# espnative-deadrail-2-3.net
KiCad netlist of a schematic drawn in EAGLE
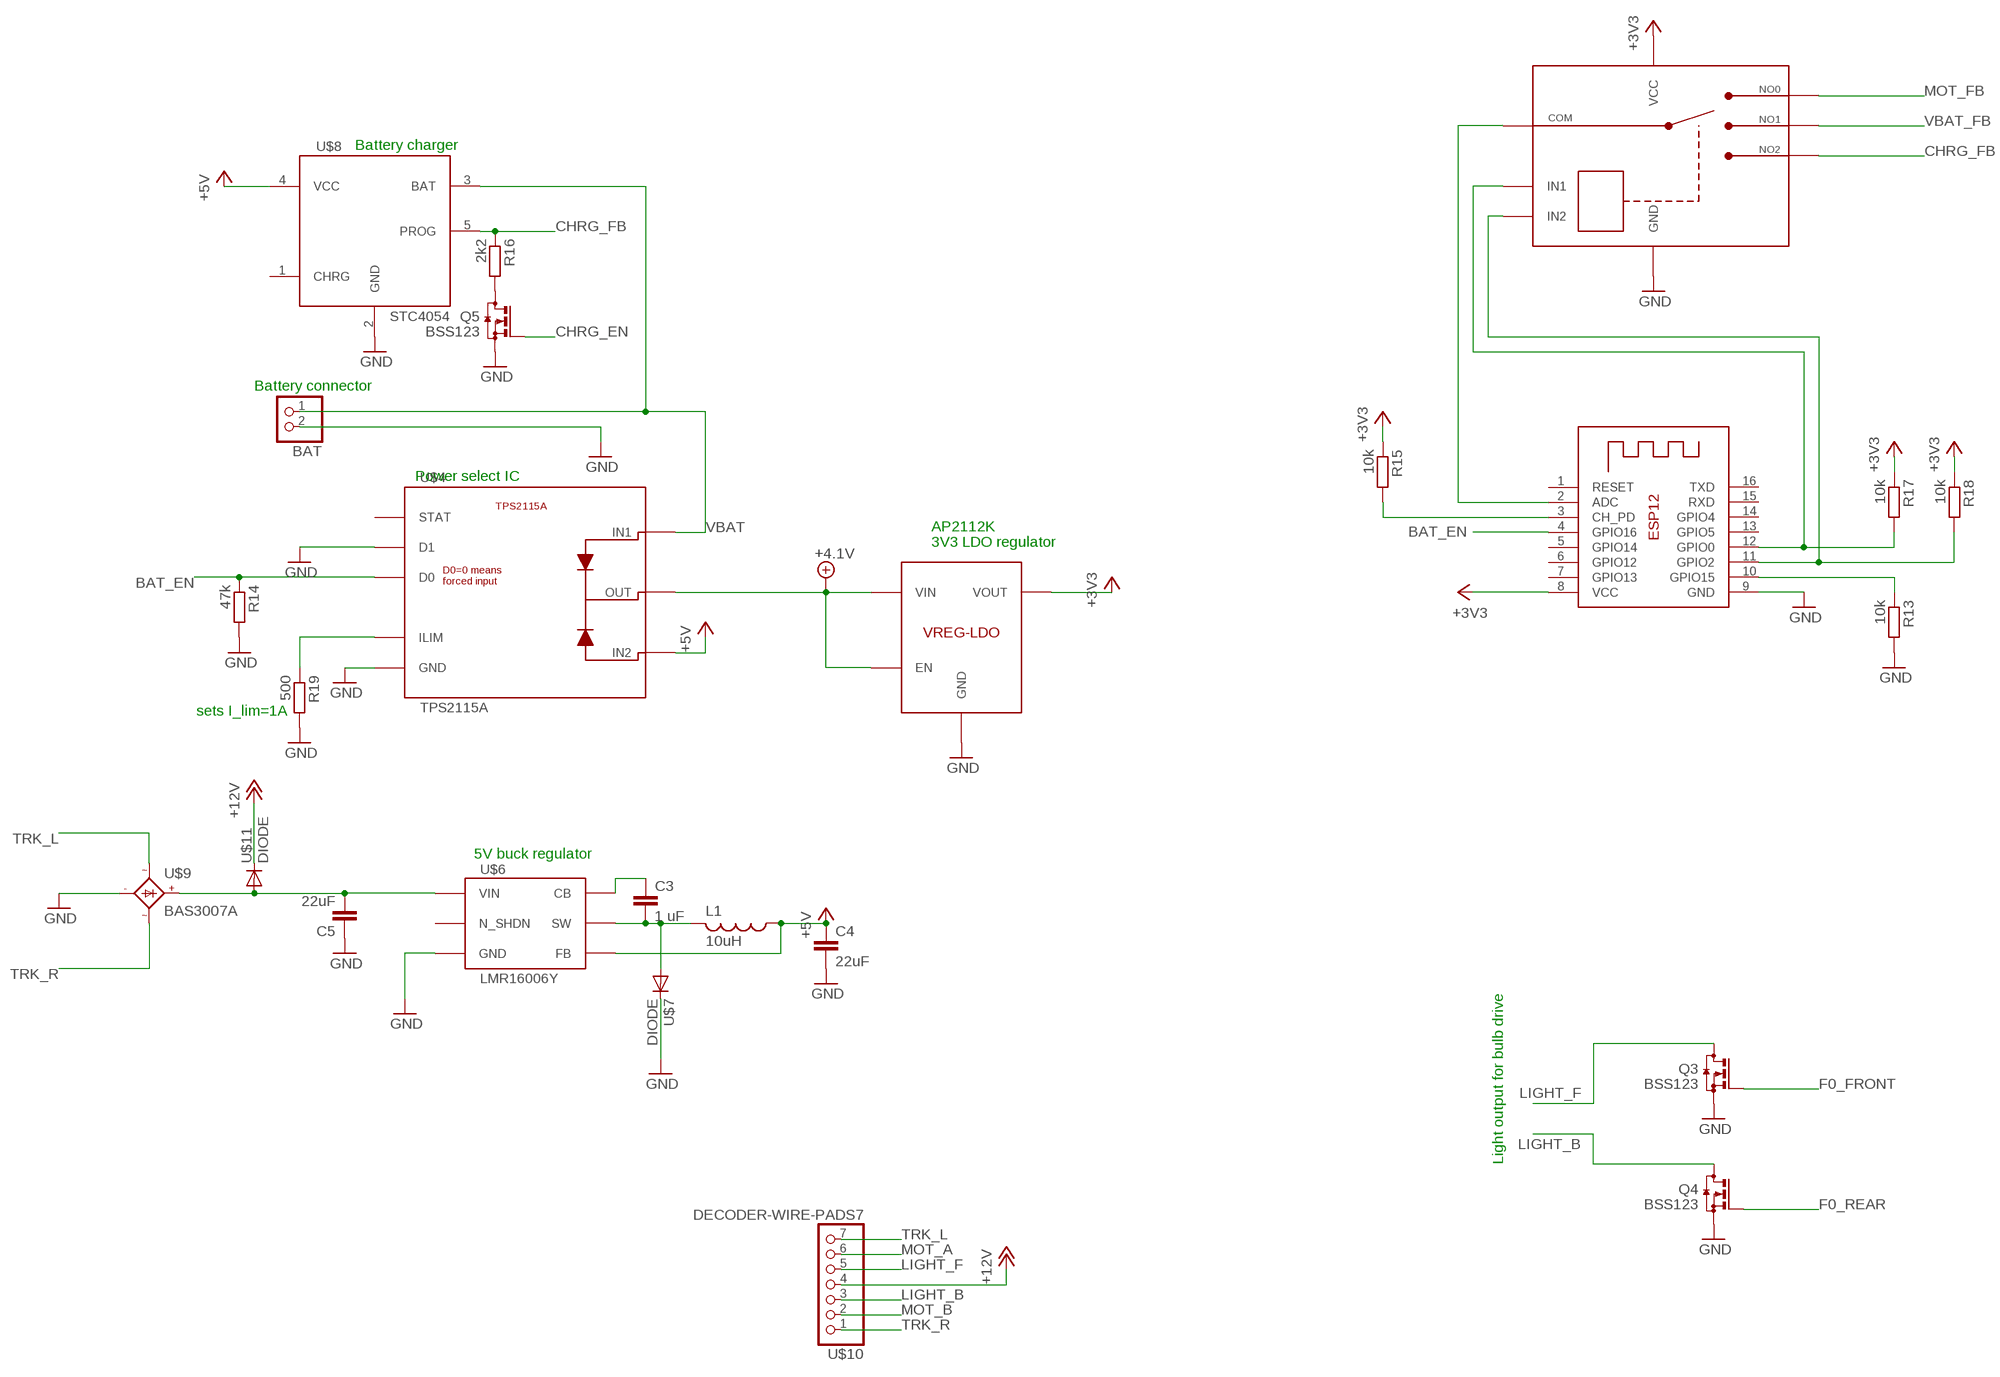
[diagram p0: schematic, sheet 1, part 1 of 2]
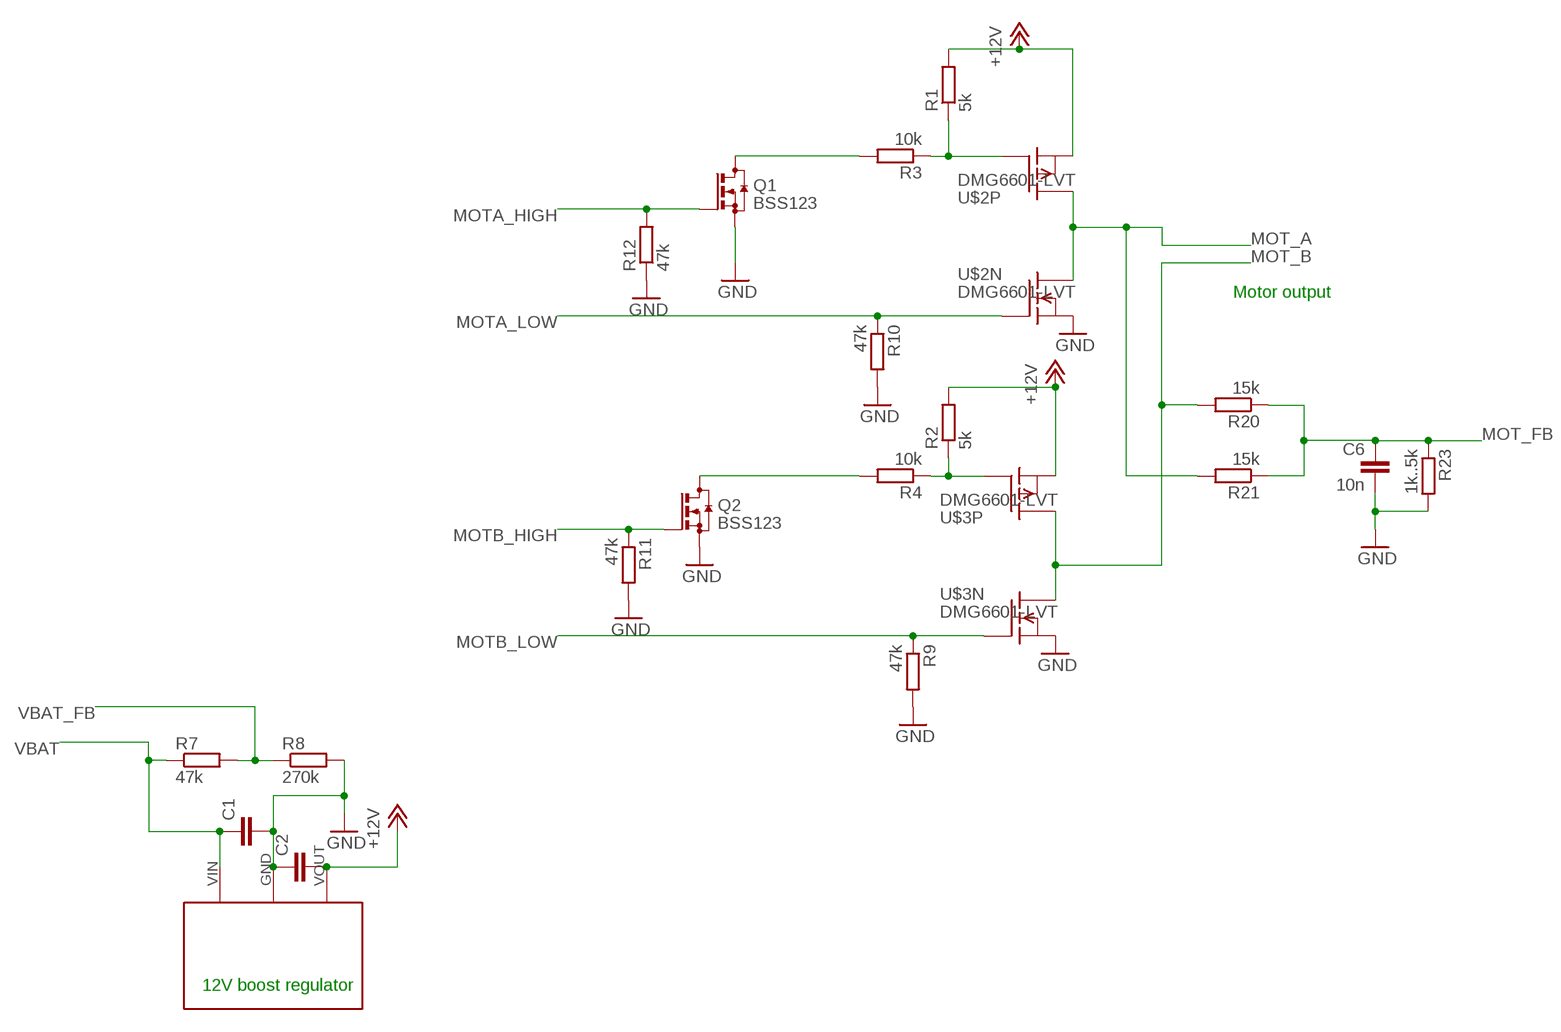
[diagram p1: schematic, sheet 1, part 2 of 2]

(export (version "E")
  (design (tool "Eeschema 10.0.6"))
  (components
    (comp (ref "BAT")
      (value "JST_2PIN-SMT-RA")
      (footprint "eagle-import:JST-PH-2-SMT-RA")
      (libsource (lib "eagle-import") (part "JST_2PIN-SMT-RA"))
    )
    (comp (ref "C1")
      (value "C-EUC1206")
      (footprint "eagle-import:C1206")
      (libsource (lib "eagle-import") (part "C-EUC1206"))
    )
    (comp (ref "C2")
      (value "C-EUC1206")
      (footprint "eagle-import:C1206")
      (libsource (lib "eagle-import") (part "C-EUC1206"))
    )
    (comp (ref "C3")
      (value "1 uF")
      (footprint "eagle-import:C0603")
      (libsource (lib "eagle-import") (part "C-EUC0603"))
    )
    (comp (ref "C4")
      (value "22uF")
      (footprint "eagle-import:C0603")
      (libsource (lib "eagle-import") (part "C-EUC0603"))
    )
    (comp (ref "C5")
      (value "22uF")
      (footprint "eagle-import:C1206")
      (libsource (lib "eagle-import") (part "C-EUC1206"))
    )
    (comp (ref "C6")
      (value "10n")
      (footprint "eagle-import:C0603")
      (libsource (lib "eagle-import") (part "C-EUC0603"))
    )
    (comp (ref "L1")
      (value "10uH")
      (footprint "eagle-import:FDSD0420")
      (libsource (lib "eagle-import") (part "FDSD0420"))
    )
    (comp (ref "Q1")
      (value "BSS123")
      (footprint "eagle-import:SOT23")
      (libsource (lib "eagle-import") (part "BSS123"))
    )
    (comp (ref "Q2")
      (value "BSS123")
      (footprint "eagle-import:SOT23")
      (libsource (lib "eagle-import") (part "BSS123"))
    )
    (comp (ref "Q3")
      (value "BSS123")
      (footprint "eagle-import:SOT23")
      (libsource (lib "eagle-import") (part "BSS123"))
    )
    (comp (ref "Q4")
      (value "BSS123")
      (footprint "eagle-import:SOT23")
      (libsource (lib "eagle-import") (part "BSS123"))
    )
    (comp (ref "Q5")
      (value "BSS123")
      (footprint "eagle-import:SOT23")
      (libsource (lib "eagle-import") (part "BSS123"))
    )
    (comp (ref "R1")
      (value "5k")
      (footprint "eagle-import:R0603")
      (libsource (lib "eagle-import") (part "R-EU_R0603"))
    )
    (comp (ref "R2")
      (value "5k")
      (footprint "eagle-import:R0603")
      (libsource (lib "eagle-import") (part "R-EU_R0603"))
    )
    (comp (ref "R3")
      (value "10k")
      (footprint "eagle-import:R0603")
      (libsource (lib "eagle-import") (part "R-EU_R0603"))
    )
    (comp (ref "R4")
      (value "10k")
      (footprint "eagle-import:R0603")
      (libsource (lib "eagle-import") (part "R-EU_R0603"))
    )
    (comp (ref "R7")
      (value "47k")
      (footprint "eagle-import:R0603")
      (libsource (lib "eagle-import") (part "R-EU_R0603"))
    )
    (comp (ref "R8")
      (value "270k")
      (footprint "eagle-import:R0603")
      (libsource (lib "eagle-import") (part "R-EU_R0603"))
    )
    (comp (ref "R9")
      (value "47k")
      (footprint "eagle-import:R0603")
      (libsource (lib "eagle-import") (part "R-EU_R0603"))
    )
    (comp (ref "R10")
      (value "47k")
      (footprint "eagle-import:R0603")
      (libsource (lib "eagle-import") (part "R-EU_R0603"))
    )
    (comp (ref "R11")
      (value "47k")
      (footprint "eagle-import:R0603")
      (libsource (lib "eagle-import") (part "R-EU_R0603"))
    )
    (comp (ref "R12")
      (value "47k")
      (footprint "eagle-import:R0603")
      (libsource (lib "eagle-import") (part "R-EU_R0603"))
    )
    (comp (ref "R13")
      (value "10k")
      (footprint "eagle-import:R0603")
      (libsource (lib "eagle-import") (part "R-EU_R0603"))
    )
    (comp (ref "R14")
      (value "47k")
      (footprint "eagle-import:R0603")
      (libsource (lib "eagle-import") (part "R-EU_R0603"))
    )
    (comp (ref "R15")
      (value "10k")
      (footprint "eagle-import:R0603")
      (libsource (lib "eagle-import") (part "R-EU_R0603"))
    )
    (comp (ref "R16")
      (value "2k2")
      (footprint "eagle-import:R0603")
      (libsource (lib "eagle-import") (part "R-EU_R0603"))
    )
    (comp (ref "R17")
      (value "10k")
      (footprint "eagle-import:R0603")
      (libsource (lib "eagle-import") (part "R-EU_R0603"))
    )
    (comp (ref "R18")
      (value "10k")
      (footprint "eagle-import:R0603")
      (libsource (lib "eagle-import") (part "R-EU_R0603"))
    )
    (comp (ref "R19")
      (value "500")
      (footprint "eagle-import:R0603")
      (libsource (lib "eagle-import") (part "R-EU_R0603"))
    )
    (comp (ref "R20")
      (value "15k")
      (footprint "eagle-import:R0603")
      (libsource (lib "eagle-import") (part "R-EU_R0603"))
    )
    (comp (ref "R21")
      (value "15k")
      (footprint "eagle-import:R0603")
      (libsource (lib "eagle-import") (part "R-EU_R0603"))
    )
    (comp (ref "R23")
      (value "1k..5k")
      (footprint "eagle-import:R0603")
      (libsource (lib "eagle-import") (part "R-EU_R0603"))
    )
    (comp (ref "U$1")
      (value "AP2112K-3V3")
      (footprint "eagle-import:SOT23-5L")
      (libsource (lib "eagle-import") (part "AP2112K"))
    )
    (comp (ref "U$2")
      (value "DMG6601-LVT")
      (footprint "eagle-import:TSOT-26")
      (libsource (lib "eagle-import") (part "DMG6601-LVT"))
    )
    (comp (ref "U$3")
      (value "DMG6601-LVT")
      (footprint "eagle-import:TSOT-26")
      (libsource (lib "eagle-import") (part "DMG6601-LVT"))
    )
    (comp (ref "U$4")
      (value "TPS2115A")
      (footprint "eagle-import:TSSOP-8")
      (libsource (lib "eagle-import") (part "TPS2115A"))
    )
    (comp (ref "U$5")
      (value "POLOLU-VREG12")
      (footprint "eagle-import:POLOLU-REGULATOR")
      (libsource (lib "eagle-import") (part "POLOLU-VREG12"))
    )
    (comp (ref "U$6")
      (value "LMR16006Y")
      (footprint "eagle-import:SOT23-6")
      (libsource (lib "eagle-import") (part "LMR16006Y"))
    )
    (comp (ref "U$7")
      (value "DIODE")
      (footprint "eagle-import:DIODE-1206")
      (libsource (lib "eagle-import") (part "DIODE"))
    )
    (comp (ref "U$8")
      (value "STC4054")
      (footprint "eagle-import:SOT23-5L")
      (libsource (lib "eagle-import") (part "STC4054"))
    )
    (comp (ref "U$9")
      (value "BAS3007A")
      (footprint "eagle-import:SOT143B")
      (libsource (lib "eagle-import") (part "BAS3007A"))
    )
    (comp (ref "U$10")
      (value "DECODER-WIRE-PADS7")
      (footprint "eagle-import:DECODER-WIRE-PADS")
      (libsource (lib "eagle-import") (part "DECODER-WIRE-PADS7"))
    )
    (comp (ref "U$11")
      (value "DIODE")
      (footprint "eagle-import:DIODE-1206")
      (libsource (lib "eagle-import") (part "DIODE"))
    )
    (comp (ref "U$12")
      (value "TS5A3359")
      (footprint "eagle-import:US8")
      (libsource (lib "eagle-import") (part "TS5A3359"))
    )
    (comp (ref "X1")
      (value "ESP-12")
      (footprint "eagle-import:ESP-12")
      (libsource (lib "eagle-import") (part "ESP-12"))
    )
  )
  (nets
    (net (code "1") (name "+3V3") (class "Default")
      (node (ref "R15") (pin "1") (pinfunction "1_1") (pintype "passive"))
      (node (ref "R17") (pin "1") (pinfunction "1_1") (pintype "passive"))
      (node (ref "R18") (pin "1") (pinfunction "1_1") (pintype "passive"))
      (node (ref "U$1") (pin "5") (pinfunction "VOUT_5") (pintype "bidirectional"))
      (node (ref "U$12") (pin "8") (pinfunction "VCC_8") (pintype "bidirectional"))
      (node (ref "X1") (pin "8") (pinfunction "VCC_8") (pintype "power_in"))
    )
    (net (code "2") (name "+4.1V") (class "Default")
      (node (ref "U$1") (pin "1") (pinfunction "VIN_1") (pintype "bidirectional"))
      (node (ref "U$1") (pin "3") (pinfunction "EN_3") (pintype "bidirectional"))
      (node (ref "U$4") (pin "7") (pinfunction "OUT_7") (pintype "bidirectional"))
    )
    (net (code "3") (name "+5V") (class "Default")
      (node (ref "C4") (pin "1") (pinfunction "1_1") (pintype "passive"))
      (node (ref "L1") (pin "P$1") (pinfunction "1_P$1") (pintype "passive"))
      (node (ref "U$4") (pin "6") (pinfunction "IN2_6") (pintype "bidirectional"))
      (node (ref "U$6") (pin "3") (pinfunction "FB_3") (pintype "bidirectional"))
      (node (ref "U$8") (pin "4") (pinfunction "VCC_4") (pintype "bidirectional"))
    )
    (net (code "4") (name "+12V") (class "Default")
      (node (ref "C2") (pin "2") (pinfunction "2_2") (pintype "passive"))
      (node (ref "R1") (pin "2") (pinfunction "2_2") (pintype "passive"))
      (node (ref "R2") (pin "2") (pinfunction "2_2") (pintype "passive"))
      (node (ref "U$10") (pin "4") (pinfunction "4_4") (pintype "passive"))
      (node (ref "U$11") (pin "C") (pinfunction "C_C") (pintype "passive"))
      (node (ref "U$2") (pin "2") (pinfunction "S_2") (pintype "passive"))
      (node (ref "U$3") (pin "2") (pinfunction "S_2") (pintype "passive"))
      (node (ref "U$5") (pin "VOUT") (pinfunction "VOUT_VOUT") (pintype "bidirectional"))
    )
    (net (code "5") (name "/BAT_EN") (class "Default")
      (node (ref "R14") (pin "1") (pinfunction "1_1") (pintype "passive"))
      (node (ref "U$4") (pin "2") (pinfunction "D0_2") (pintype "bidirectional"))
      (node (ref "X1") (pin "4") (pinfunction "GPIO16_4") (pintype "bidirectional"))
    )
    (net (code "6") (name "/CHRG_EN") (class "Default")
      (node (ref "Q5") (pin "1") (pinfunction "G_1") (pintype "passive"))
    )
    (net (code "7") (name "/CHRG_FB") (class "Default")
      (node (ref "R16") (pin "1") (pinfunction "1_1") (pintype "passive"))
      (node (ref "U$12") (pin "3") (pinfunction "NO2_3") (pintype "bidirectional"))
      (node (ref "U$8") (pin "5") (pinfunction "PROG_5") (pintype "bidirectional"))
    )
    (net (code "8") (name "/F0_FRONT") (class "Default")
      (node (ref "Q3") (pin "1") (pinfunction "G_1") (pintype "passive"))
    )
    (net (code "9") (name "/F0_REAR") (class "Default")
      (node (ref "Q4") (pin "1") (pinfunction "G_1") (pintype "passive"))
    )
    (net (code "10") (name "/LIGHT_B") (class "Default")
      (node (ref "Q4") (pin "3") (pinfunction "D_3") (pintype "passive"))
      (node (ref "U$10") (pin "3") (pinfunction "3_3") (pintype "passive"))
    )
    (net (code "11") (name "/LIGHT_F") (class "Default")
      (node (ref "Q3") (pin "3") (pinfunction "D_3") (pintype "passive"))
      (node (ref "U$10") (pin "5") (pinfunction "5_5") (pintype "passive"))
    )
    (net (code "12") (name "/MOTA_HIGH") (class "Default")
      (node (ref "Q1") (pin "1") (pinfunction "G_1") (pintype "passive"))
      (node (ref "R12") (pin "2") (pinfunction "2_2") (pintype "passive"))
    )
    (net (code "13") (name "/MOTA_LOW") (class "Default")
      (node (ref "R10") (pin "1") (pinfunction "1_1") (pintype "passive"))
      (node (ref "U$2") (pin "1") (pinfunction "G_1") (pintype "passive"))
    )
    (net (code "14") (name "/MOTB_HIGH") (class "Default")
      (node (ref "Q2") (pin "1") (pinfunction "G_1") (pintype "passive"))
      (node (ref "R11") (pin "1") (pinfunction "1_1") (pintype "passive"))
    )
    (net (code "15") (name "/MOTB_LOW") (class "Default")
      (node (ref "R9") (pin "1") (pinfunction "1_1") (pintype "passive"))
      (node (ref "U$3") (pin "1") (pinfunction "G_1") (pintype "passive"))
    )
    (net (code "16") (name "/MOT_A") (class "Default")
      (node (ref "R21") (pin "2") (pinfunction "2_2") (pintype "passive"))
      (node (ref "U$10") (pin "6") (pinfunction "6_6") (pintype "passive"))
      (node (ref "U$2") (pin "4") (pinfunction "D_4") (pintype "passive"))
      (node (ref "U$2") (pin "6") (pinfunction "D_6") (pintype "passive"))
    )
    (net (code "17") (name "/MOT_B") (class "Default")
      (node (ref "R20") (pin "2") (pinfunction "2_2") (pintype "passive"))
      (node (ref "U$10") (pin "2") (pinfunction "2_2") (pintype "passive"))
      (node (ref "U$3") (pin "4") (pinfunction "D_4") (pintype "passive"))
      (node (ref "U$3") (pin "6") (pinfunction "D_6") (pintype "passive"))
    )
    (net (code "18") (name "/MOT_FB") (class "Default")
      (node (ref "C6") (pin "1") (pinfunction "1_1") (pintype "passive"))
      (node (ref "R20") (pin "1") (pinfunction "1_1") (pintype "passive"))
      (node (ref "R21") (pin "1") (pinfunction "1_1") (pintype "passive"))
      (node (ref "R23") (pin "1") (pinfunction "1_1") (pintype "passive"))
      (node (ref "U$12") (pin "1") (pinfunction "NO0_1") (pintype "bidirectional"))
    )
    (net (code "19") (name "/TRK_L") (class "Default")
      (node (ref "U$10") (pin "7") (pinfunction "7_7") (pintype "passive"))
      (node (ref "U$9") (pin "2") (pinfunction "AC1_2") (pintype "passive"))
    )
    (net (code "20") (name "/TRK_R") (class "Default")
      (node (ref "U$10") (pin "1") (pinfunction "1_1") (pintype "passive"))
      (node (ref "U$9") (pin "3") (pinfunction "AC2_3") (pintype "passive"))
    )
    (net (code "21") (name "/VBAT") (class "Default")
      (node (ref "BAT") (pin "1") (pinfunction "2_1") (pintype "passive"))
      (node (ref "C1") (pin "1") (pinfunction "1_1") (pintype "passive"))
      (node (ref "R7") (pin "1") (pinfunction "1_1") (pintype "passive"))
      (node (ref "U$4") (pin "8") (pinfunction "IN1_8") (pintype "bidirectional"))
      (node (ref "U$5") (pin "VIN") (pinfunction "VIN_VIN") (pintype "bidirectional"))
      (node (ref "U$8") (pin "3") (pinfunction "BAT_3") (pintype "bidirectional"))
    )
    (net (code "22") (name "/VBAT_FB") (class "Default")
      (node (ref "R7") (pin "2") (pinfunction "2_2") (pintype "passive"))
      (node (ref "R8") (pin "1") (pinfunction "1_1") (pintype "passive"))
      (node (ref "U$12") (pin "2") (pinfunction "NO1_2") (pintype "bidirectional"))
    )
    (net (code "23") (name "GND") (class "Default")
      (node (ref "BAT") (pin "2") (pinfunction "1_2") (pintype "passive"))
      (node (ref "C1") (pin "2") (pinfunction "2_2") (pintype "passive"))
      (node (ref "C2") (pin "1") (pinfunction "1_1") (pintype "passive"))
      (node (ref "C4") (pin "2") (pinfunction "2_2") (pintype "passive"))
      (node (ref "C5") (pin "1") (pinfunction "1_1") (pintype "passive"))
      (node (ref "C6") (pin "2") (pinfunction "2_2") (pintype "passive"))
      (node (ref "Q1") (pin "2") (pinfunction "S_2") (pintype "passive"))
      (node (ref "Q2") (pin "2") (pinfunction "S_2") (pintype "passive"))
      (node (ref "Q3") (pin "2") (pinfunction "S_2") (pintype "passive"))
      (node (ref "Q4") (pin "2") (pinfunction "S_2") (pintype "passive"))
      (node (ref "Q5") (pin "2") (pinfunction "S_2") (pintype "passive"))
      (node (ref "R10") (pin "2") (pinfunction "2_2") (pintype "passive"))
      (node (ref "R11") (pin "2") (pinfunction "2_2") (pintype "passive"))
      (node (ref "R12") (pin "1") (pinfunction "1_1") (pintype "passive"))
      (node (ref "R13") (pin "2") (pinfunction "2_2") (pintype "passive"))
      (node (ref "R14") (pin "2") (pinfunction "2_2") (pintype "passive"))
      (node (ref "R19") (pin "2") (pinfunction "2_2") (pintype "passive"))
      (node (ref "R23") (pin "2") (pinfunction "2_2") (pintype "passive"))
      (node (ref "R8") (pin "2") (pinfunction "2_2") (pintype "passive"))
      (node (ref "R9") (pin "2") (pinfunction "2_2") (pintype "passive"))
      (node (ref "U$1") (pin "2") (pinfunction "GND_2") (pintype "bidirectional"))
      (node (ref "U$12") (pin "4") (pinfunction "GND_4") (pintype "bidirectional"))
      (node (ref "U$2") (pin "5") (pinfunction "S_5") (pintype "passive"))
      (node (ref "U$3") (pin "5") (pinfunction "S_5") (pintype "passive"))
      (node (ref "U$4") (pin "3") (pinfunction "D1_3") (pintype "bidirectional"))
      (node (ref "U$4") (pin "5") (pinfunction "GND_5") (pintype "bidirectional"))
      (node (ref "U$5") (pin "GND") (pinfunction "GND_GND") (pintype "bidirectional"))
      (node (ref "U$6") (pin "2") (pinfunction "GND_2") (pintype "bidirectional"))
      (node (ref "U$7") (pin "C") (pinfunction "C_C") (pintype "passive"))
      (node (ref "U$8") (pin "2") (pinfunction "GND_2") (pintype "bidirectional"))
      (node (ref "U$9") (pin "1") (pinfunction "-_1") (pintype "passive"))
      (node (ref "X1") (pin "9") (pinfunction "GND_9") (pintype "power_in"))
    )
    (net (code "24") (name "Net-(L1-2)") (class "Default")
      (node (ref "C3") (pin "2") (pinfunction "2_2") (pintype "passive"))
      (node (ref "L1") (pin "P$2") (pinfunction "2_P$2") (pintype "passive"))
      (node (ref "U$6") (pin "6") (pinfunction "SW_6") (pintype "bidirectional"))
      (node (ref "U$7") (pin "A") (pinfunction "A_A") (pintype "passive"))
    )
    (net (code "25") (name "Net-(Q1-D)") (class "Default")
      (node (ref "Q1") (pin "3") (pinfunction "D_3") (pintype "passive"))
      (node (ref "R3") (pin "2") (pinfunction "2_2") (pintype "passive"))
    )
    (net (code "26") (name "Net-(Q2-D)") (class "Default")
      (node (ref "Q2") (pin "3") (pinfunction "D_3") (pintype "passive"))
      (node (ref "R4") (pin "2") (pinfunction "2_2") (pintype "passive"))
    )
    (net (code "27") (name "Net-(Q5-D)") (class "Default")
      (node (ref "Q5") (pin "3") (pinfunction "D_3") (pintype "passive"))
      (node (ref "R16") (pin "2") (pinfunction "2_2") (pintype "passive"))
    )
    (net (code "28") (name "Net-(U$2B-G)") (class "Default")
      (node (ref "R1") (pin "1") (pinfunction "1_1") (pintype "passive"))
      (node (ref "R3") (pin "1") (pinfunction "1_1") (pintype "passive"))
      (node (ref "U$2") (pin "3") (pinfunction "G_3") (pintype "passive"))
    )
    (net (code "29") (name "Net-(U$3B-G)") (class "Default")
      (node (ref "R2") (pin "1") (pinfunction "1_1") (pintype "passive"))
      (node (ref "R4") (pin "1") (pinfunction "1_1") (pintype "passive"))
      (node (ref "U$3") (pin "3") (pinfunction "G_3") (pintype "passive"))
    )
    (net (code "30") (name "Net-(U$4-ILIM)") (class "Default")
      (node (ref "R19") (pin "1") (pinfunction "1_1") (pintype "passive"))
      (node (ref "U$4") (pin "4") (pinfunction "ILIM_4") (pintype "bidirectional"))
    )
    (net (code "31") (name "Net-(U$6-CB)") (class "Default")
      (node (ref "C3") (pin "1") (pinfunction "1_1") (pintype "passive"))
      (node (ref "U$6") (pin "1") (pinfunction "CB_1") (pintype "bidirectional"))
    )
    (net (code "32") (name "Net-(U$6-VIN)") (class "Default")
      (node (ref "C5") (pin "2") (pinfunction "2_2") (pintype "passive"))
      (node (ref "U$11") (pin "A") (pinfunction "A_A") (pintype "passive"))
      (node (ref "U$6") (pin "5") (pinfunction "VIN_5") (pintype "bidirectional"))
      (node (ref "U$9") (pin "4") (pinfunction "+_4") (pintype "passive"))
    )
    (net (code "33") (name "Net-(U$12-COM)") (class "Default")
      (node (ref "U$12") (pin "7") (pinfunction "COM_7") (pintype "bidirectional"))
      (node (ref "X1") (pin "2") (pinfunction "ADC_2") (pintype "passive"))
    )
    (net (code "34") (name "Net-(U$12-IN1)") (class "Default")
      (node (ref "R17") (pin "2") (pinfunction "2_2") (pintype "passive"))
      (node (ref "U$12") (pin "6") (pinfunction "IN1_6") (pintype "bidirectional"))
      (node (ref "X1") (pin "12") (pinfunction "GPIO0_12") (pintype "bidirectional"))
    )
    (net (code "35") (name "Net-(U$12-IN2)") (class "Default")
      (node (ref "R18") (pin "2") (pinfunction "2_2") (pintype "passive"))
      (node (ref "U$12") (pin "5") (pinfunction "IN2_5") (pintype "bidirectional"))
      (node (ref "X1") (pin "11") (pinfunction "GPIO2_11") (pintype "bidirectional"))
    )
    (net (code "36") (name "Net-(X1-CH_PD)") (class "Default")
      (node (ref "R15") (pin "2") (pinfunction "2_2") (pintype "passive"))
      (node (ref "X1") (pin "3") (pinfunction "CH_PD_3") (pintype "input"))
    )
    (net (code "37") (name "Net-(X1-GPIO15)") (class "Default")
      (node (ref "R13") (pin "1") (pinfunction "1_1") (pintype "passive"))
      (node (ref "X1") (pin "10") (pinfunction "GPIO15_10") (pintype "bidirectional"))
    )
    (net (code "38") (name "unconnected-(U$4-STAT-Pad1)") (class "Default")
      (node (ref "U$4") (pin "1") (pinfunction "STAT_1") (pintype "bidirectional"))
    )
    (net (code "39") (name "unconnected-(U$6-N_SHDN-Pad4)") (class "Default")
      (node (ref "U$6") (pin "4") (pinfunction "N_SHDN_4") (pintype "bidirectional"))
    )
    (net (code "40") (name "unconnected-(U$8-CHRG-Pad1)") (class "Default")
      (node (ref "U$8") (pin "1") (pinfunction "CHRG_1") (pintype "bidirectional"))
    )
    (net (code "41") (name "unconnected-(X1-GPIO4-Pad14)") (class "Default")
      (node (ref "X1") (pin "14") (pinfunction "GPIO4_14") (pintype "bidirectional"))
    )
    (net (code "42") (name "unconnected-(X1-GPIO5-Pad13)") (class "Default")
      (node (ref "X1") (pin "13") (pinfunction "GPIO5_13") (pintype "bidirectional"))
    )
    (net (code "43") (name "unconnected-(X1-GPIO12-Pad6)") (class "Default")
      (node (ref "X1") (pin "6") (pinfunction "GPIO12_6") (pintype "bidirectional"))
    )
    (net (code "44") (name "unconnected-(X1-GPIO13-Pad7)") (class "Default")
      (node (ref "X1") (pin "7") (pinfunction "GPIO13_7") (pintype "bidirectional"))
    )
    (net (code "45") (name "unconnected-(X1-GPIO14-Pad5)") (class "Default")
      (node (ref "X1") (pin "5") (pinfunction "GPIO14_5") (pintype "bidirectional"))
    )
    (net (code "46") (name "unconnected-(X1-RESET-Pad1)") (class "Default")
      (node (ref "X1") (pin "1") (pinfunction "RESET_1") (pintype "input"))
    )
    (net (code "47") (name "unconnected-(X1-RXD-Pad15)") (class "Default")
      (node (ref "X1") (pin "15") (pinfunction "RXD_15") (pintype "input"))
    )
    (net (code "48") (name "unconnected-(X1-TXD-Pad16)") (class "Default")
      (node (ref "X1") (pin "16") (pinfunction "TXD_16") (pintype "output"))
    )
  )
)
